# SAFETY_SWITCH.net
KiCad netlist of a schematic drawn in Altium Designer
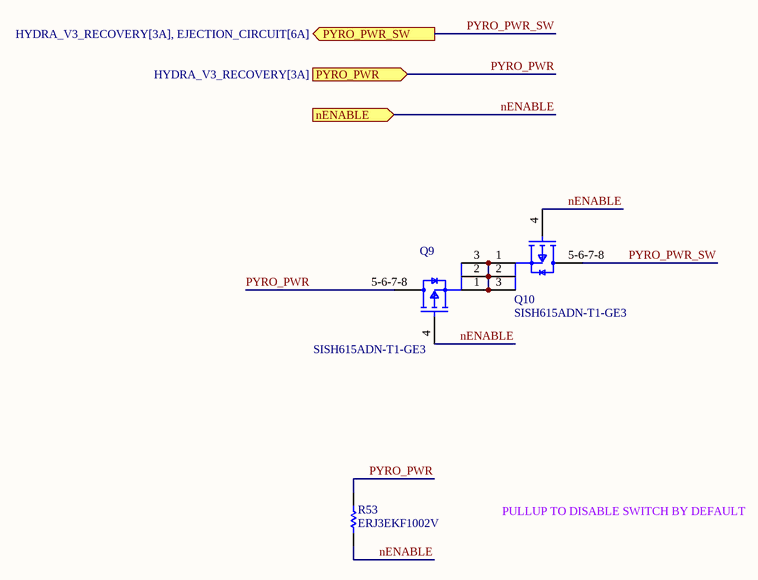
[diagram p0: SAFETY_SWITCH.SchDoc]

(export (version "E")
  (design (tool "Eeschema 10.0.6"))
  (components
    (comp (ref "Q9")
      (value "SISH615ADN-T1-GE3")
      (footprint "SISH615ADN-T1-GE3-Footprint-1")
      (description "Trans MOSFET P-CH 20V 22.1A 8-Pin PowerPAK 1212 EP T/R")
      (libsource (lib "uORocketry Hardware") (part "SISH615ADN-T1-GE3-Symbol-1"))
    )
    (comp (ref "Q10")
      (value "SISH615ADN-T1-GE3")
      (footprint "SISH615ADN-T1-GE3-Footprint-1")
      (description "Trans MOSFET P-CH 20V 22.1A 8-Pin PowerPAK 1212 EP T/R")
      (libsource (lib "uORocketry Hardware") (part "SISH615ADN-T1-GE3-Symbol-1"))
    )
    (comp (ref "R53")
      (value "ERJ3EKF1002V")
      (footprint "RESC1609X55X30LL15T15")
      (description "Chip Resistor, 10 KOhm, +/- 1%, 0.1 W, -55 to 155 degC, 0603 (1608 Metric), RoHS, Tape and Reel")
      (fields (field (name "TOLERANCE") "1%") (field (name "MANUFACTURER") "Panasonic"))
      (libsource (lib "Altium Content Vault") (part "RES-2"))
    )
  )
  (nets
    (net (code "1") (name "/PYRO_PWR") (class "Default")
      (node (ref "Q9") (pin "5-6-7-8") (pinfunction "D_5-6-7-8") (pintype "passive"))
      (node (ref "R53") (pin "1") (pinfunction "1_1") (pintype "passive"))
    )
    (net (code "2") (name "/PYRO_PWR_SW") (class "Default")
      (node (ref "Q10") (pin "5-6-7-8") (pinfunction "D_5-6-7-8") (pintype "passive"))
    )
    (net (code "3") (name "/nENABLE") (class "Default")
      (node (ref "Q10") (pin "4") (pinfunction "G_4") (pintype "passive"))
      (node (ref "Q9") (pin "4") (pinfunction "G_4") (pintype "passive"))
      (node (ref "R53") (pin "2") (pinfunction "2_2") (pintype "passive"))
    )
    (net (code "4") (name "Net-(Q10-S-Pad1)") (class "Default")
      (node (ref "Q10") (pin "1") (pinfunction "S_1") (pintype "passive"))
      (node (ref "Q10") (pin "2") (pinfunction "S_2") (pintype "passive"))
      (node (ref "Q10") (pin "3") (pinfunction "S_3") (pintype "passive"))
      (node (ref "Q9") (pin "1") (pinfunction "S_1") (pintype "passive"))
      (node (ref "Q9") (pin "2") (pinfunction "S_2") (pintype "passive"))
      (node (ref "Q9") (pin "3") (pinfunction "S_3") (pintype "passive"))
    )
  )
)
